# LG_TRACKER_Block_Diagram.net
KiCad netlist of a schematic drawn in Altium Designer
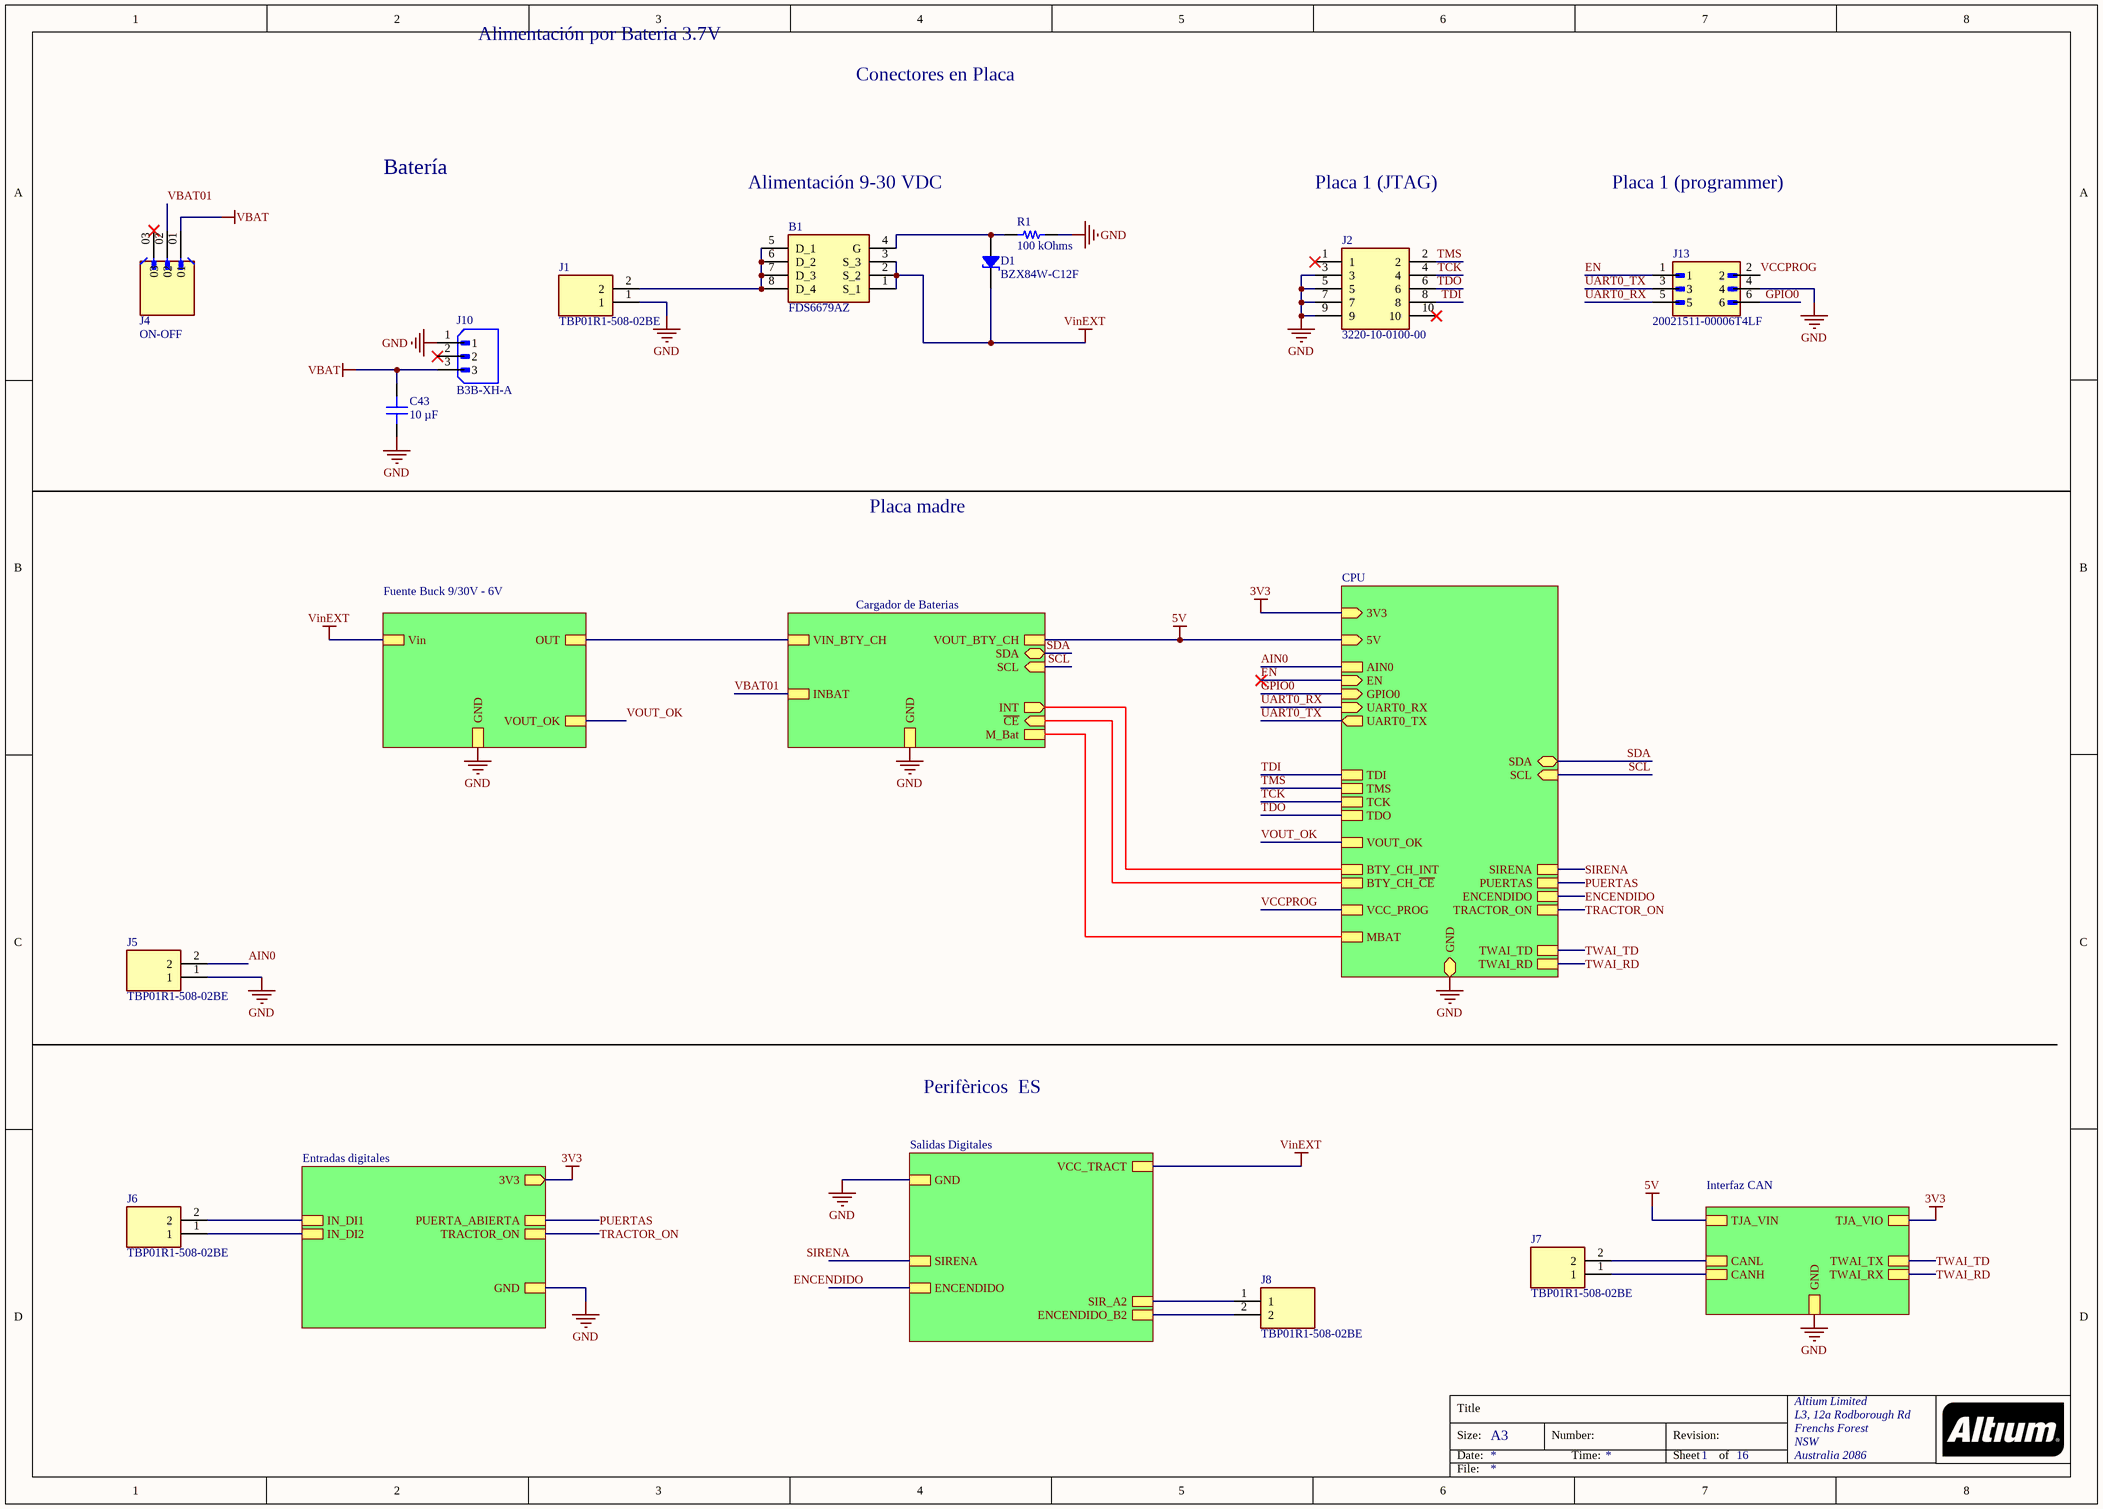
[diagram p0: LG_TRACKER_Block_Diagram.SchDoc]

(export (version "E")
  (design (tool "Eeschema 10.0.6"))
  (components
    (comp (ref "B1")
      (value "FDS6679AZ")
      (footprint "SOIC127P600X175-8N:SOIC127P600X175-8N")
      (fields (field (name "MOUSER PART NUMBER") "512-FDS6679AZ"))
      (libsource (lib "FDS6679AZ") (part "FDS6679AZ"))
    )
    (comp (ref "C43")
      (value "10 µF")
      (footprint "PCB - RESISTOR - CHIP - YAGEO RES 0805_2012:YAGEO RES 0805_2012")
      (description "CAP CER 10UF 16V X5R 0805")
      (fields
        (field (name "PART NUMBER") "CL21A106KOQNNNE")
        (field (name "MANUFACTURER") "Samsung Electro-Mechanics")
      )
      (libsource (lib "Celestial Altium Library - altium_library") (part "Capacitor"))
    )
    (comp (ref "D1")
      (value "BZX84W-C12F")
      (footprint "SOT65P210X110-3N")
      (description "DIODE ZENER 12V 275MW SOT323")
      (fields (field (name "MANUFACTURER") "Nexperia USA Inc.") (field (name "TOLERANCE") "±5%"))
      (libsource (lib "Celestial Altium Library - altium_library") (part "Diode Zener"))
    )
    (comp (ref "J1")
      (value "TBP01R1-508-02BE")
      (footprint "CUI_TBP01R1-508-02BE")
      (description "2~24 Poles, Pluggable, Receptacle, Horizontal, 5.08 Pitch, Terminal Block Connector")
      (fields (field (name "MF") "Same Sky"))
      (libsource (lib "TBP01R1-508-02BE") (part "TBP01R1-508-02BE"))
    )
    (comp (ref "J2")
      (value "3220-10-0100-00")
      (footprint "322010010000")
      (description "Connector Header Through Hole 10 position Shrouded 4 wall 0.050\" (1.27mm)")
      (libsource (lib "DIN_DC_Base_Board_components") (part "3220-10-0100-00"))
    )
    (comp (ref "J4")
      (value "ON-OFF")
      (footprint "AMPHENOL_68001-203HLF")
      (fields (field (name "MF") "Amphenol ICC") (field (name "MP") "68001-203HLF"))
      (libsource (lib "68001-203HLF") (part "68001-203HLF"))
    )
    (comp (ref "J5")
      (value "TBP01R1-508-02BE")
      (footprint "CUI_TBP01R1-508-02BE")
      (description "2~24 Poles, Pluggable, Receptacle, Horizontal, 5.08 Pitch, Terminal Block Connector")
      (fields (field (name "MF") "Same Sky"))
      (libsource (lib "TBP01R1-508-02BE") (part "TBP01R1-508-02BE"))
    )
    (comp (ref "J6")
      (value "TBP01R1-508-02BE")
      (footprint "CUI_TBP01R1-508-02BE")
      (description "2~24 Poles, Pluggable, Receptacle, Horizontal, 5.08 Pitch, Terminal Block Connector")
      (fields (field (name "MF") "Same Sky"))
      (libsource (lib "TBP01R1-508-02BE") (part "TBP01R1-508-02BE"))
    )
    (comp (ref "J7")
      (value "TBP01R1-508-02BE")
      (footprint "CUI_TBP01R1-508-02BE")
      (description "2~24 Poles, Pluggable, Receptacle, Horizontal, 5.08 Pitch, Terminal Block Connector")
      (fields (field (name "MF") "Same Sky"))
      (libsource (lib "TBP01R1-508-02BE") (part "TBP01R1-508-02BE"))
    )
    (comp (ref "J8")
      (value "TBP01R1-508-02BE")
      (footprint "CUI_TBP01R1-508-02BE")
      (description "2~24 Poles, Pluggable, Receptacle, Horizontal, 5.08 Pitch, Terminal Block Connector")
      (fields (field (name "MF") "Same Sky"))
      (libsource (lib "") (part "TBP01R1-508-02BE_1"))
    )
    (comp (ref "J10")
      (value "B3B-XH-A")
      (footprint "JST_B3B-XH-A")
      (description "Connector Header Through Hole 3 position 0.098 (2.50mm)")
      (fields (field (name "MF") "JST Sales"))
      (libsource (lib "B3B-XH-A") (part "B3B-XH-A"))
    )
    (comp (ref "J13")
      (value "20021511-00006T4LF")
      (footprint "AMPHENOL_20021511-00006T4LF")
      (description "1.27mm (0.05in.) pitch, Shrouded header, 6 contacts")
      (fields (field (name "MF") "Amphenol ICC (FCI)"))
      (libsource (lib "DIN_DC_Base_Board_components") (part "20021511-00006T4LF"))
    )
    (comp (ref "R1")
      (value "100 kOhms")
      (footprint "RES 0603_1608")
      (description "RES 100K OHM 0.1% 1/16W 0603")
      (fields
        (field (name "PART NUMBER") "RNCS0603BKE100K")
        (field (name "MANUFACTURER") "Stackpole Electronics Inc")
      )
      (libsource (lib "Celestial Altium Library - altium_library") (part "Resistor"))
    )
  )
  (nets
    (net (code "1") (name "/AIN0") (class "Default")
      (node (ref "J5") (pin "2") (pinfunction "2_2") (pintype "passive"))
    )
    (net (code "3") (name "/CANH") (class "Default")
      (node (ref "J7") (pin "1") (pinfunction "1_1") (pintype "passive"))
    )
    (net (code "4") (name "/CANL") (class "Default")
      (node (ref "J7") (pin "2") (pinfunction "2_2") (pintype "passive"))
    )
    (net (code "5") (name "/EN") (class "Default")
      (node (ref "J13") (pin "1") (pinfunction "1_1") (pintype "passive+no_connect"))
    )
    (net (code "7") (name "/ENCENDIDO_B2") (class "Default")
      (node (ref "J8") (pin "2") (pinfunction "2_2") (pintype "passive"))
    )
    (net (code "8") (name "/GPIO0") (class "Default")
      (node (ref "J13") (pin "6") (pinfunction "6_6") (pintype "passive"))
    )
    (net (code "10") (name "/IN_DI1") (class "Default")
      (node (ref "J6") (pin "2") (pinfunction "2_2") (pintype "passive"))
    )
    (net (code "11") (name "/IN_DI2") (class "Default")
      (node (ref "J6") (pin "1") (pinfunction "1_1") (pintype "passive"))
    )
    (net (code "18") (name "/SIR_A2") (class "Default")
      (node (ref "J8") (pin "1") (pinfunction "1_1") (pintype "passive"))
    )
    (net (code "19") (name "/TCK") (class "Default")
      (node (ref "J2") (pin "4") (pinfunction "4_4") (pintype "passive"))
    )
    (net (code "20") (name "/TDI") (class "Default")
      (node (ref "J2") (pin "8") (pinfunction "8_8") (pintype "passive"))
    )
    (net (code "21") (name "/TDO") (class "Default")
      (node (ref "J2") (pin "6") (pinfunction "6_6") (pintype "passive"))
    )
    (net (code "22") (name "/TMS") (class "Default")
      (node (ref "J2") (pin "2") (pinfunction "2_2") (pintype "passive"))
    )
    (net (code "26") (name "/UART0_RX") (class "Default")
      (node (ref "J13") (pin "5") (pinfunction "5_5") (pintype "passive"))
    )
    (net (code "27") (name "/UART0_TX") (class "Default")
      (node (ref "J13") (pin "3") (pinfunction "3_3") (pintype "passive"))
    )
    (net (code "28") (name "/VBAT01") (class "Default")
      (node (ref "J4") (pin "02") (pinfunction "02_02") (pintype "passive"))
    )
    (net (code "29") (name "/VCCPROG") (class "Default")
      (node (ref "J13") (pin "2") (pinfunction "2_2") (pintype "passive"))
    )
    (net (code "33") (name "GND") (class "Default")
      (node (ref "C43") (pin "1") (pinfunction "1_1") (pintype "passive"))
      (node (ref "J1") (pin "1") (pinfunction "1_1") (pintype "passive"))
      (node (ref "J10") (pin "1") (pinfunction "1_1") (pintype "passive"))
      (node (ref "J13") (pin "4") (pinfunction "4_4") (pintype "passive"))
      (node (ref "J2") (pin "3") (pinfunction "3_3") (pintype "passive"))
      (node (ref "J2") (pin "5") (pinfunction "5_5") (pintype "passive"))
      (node (ref "J2") (pin "7") (pinfunction "7_7") (pintype "passive"))
      (node (ref "J2") (pin "9") (pinfunction "9_9") (pintype "passive"))
      (node (ref "J5") (pin "1") (pinfunction "1_1") (pintype "passive"))
      (node (ref "R1") (pin "1") (pinfunction "1_1") (pintype "passive"))
    )
    (net (code "34") (name "Net-(B1-D_1)") (class "Default")
      (node (ref "B1") (pin "5") (pinfunction "D_1_5") (pintype "passive"))
      (node (ref "B1") (pin "6") (pinfunction "D_2_6") (pintype "passive"))
      (node (ref "B1") (pin "7") (pinfunction "D_3_7") (pintype "passive"))
      (node (ref "B1") (pin "8") (pinfunction "D_4_8") (pintype "passive"))
      (node (ref "J1") (pin "2") (pinfunction "2_2") (pintype "passive"))
    )
    (net (code "35") (name "Net-(B1-G)") (class "Default")
      (node (ref "B1") (pin "4") (pinfunction "G_4") (pintype "passive"))
      (node (ref "D1") (pin "1") (pinfunction "1_1") (pintype "passive"))
      (node (ref "R1") (pin "2") (pinfunction "2_2") (pintype "passive"))
    )
    (net (code "36") (name "VBAT") (class "Default")
      (node (ref "C43") (pin "2") (pinfunction "2_2") (pintype "passive"))
      (node (ref "J10") (pin "3") (pinfunction "3_3") (pintype "passive"))
      (node (ref "J4") (pin "01") (pinfunction "01_01") (pintype "passive"))
    )
    (net (code "37") (name "VinEXT") (class "Default")
      (node (ref "B1") (pin "1") (pinfunction "S_1_1") (pintype "passive"))
      (node (ref "B1") (pin "2") (pinfunction "S_2_2") (pintype "passive"))
      (node (ref "B1") (pin "3") (pinfunction "S_3_3") (pintype "passive"))
      (node (ref "D1") (pin "2") (pinfunction "2_2") (pintype "passive"))
    )
    (net (code "38") (name "unconnected-(J2-Pad1)") (class "Default")
      (node (ref "J2") (pin "1") (pinfunction "1_1") (pintype "passive+no_connect"))
    )
    (net (code "39") (name "unconnected-(J2-Pad10)") (class "Default")
      (node (ref "J2") (pin "10") (pinfunction "10_10") (pintype "passive+no_connect"))
    )
    (net (code "40") (name "unconnected-(J4-Pad03)") (class "Default")
      (node (ref "J4") (pin "03") (pinfunction "03_03") (pintype "passive+no_connect"))
    )
    (net (code "41") (name "unconnected-(J10-Pad2)") (class "Default")
      (node (ref "J10") (pin "2") (pinfunction "2_2") (pintype "passive+no_connect"))
    )
  )
)
